# Digital_IO.net
KiCad netlist of a schematic drawn in Altium Designer
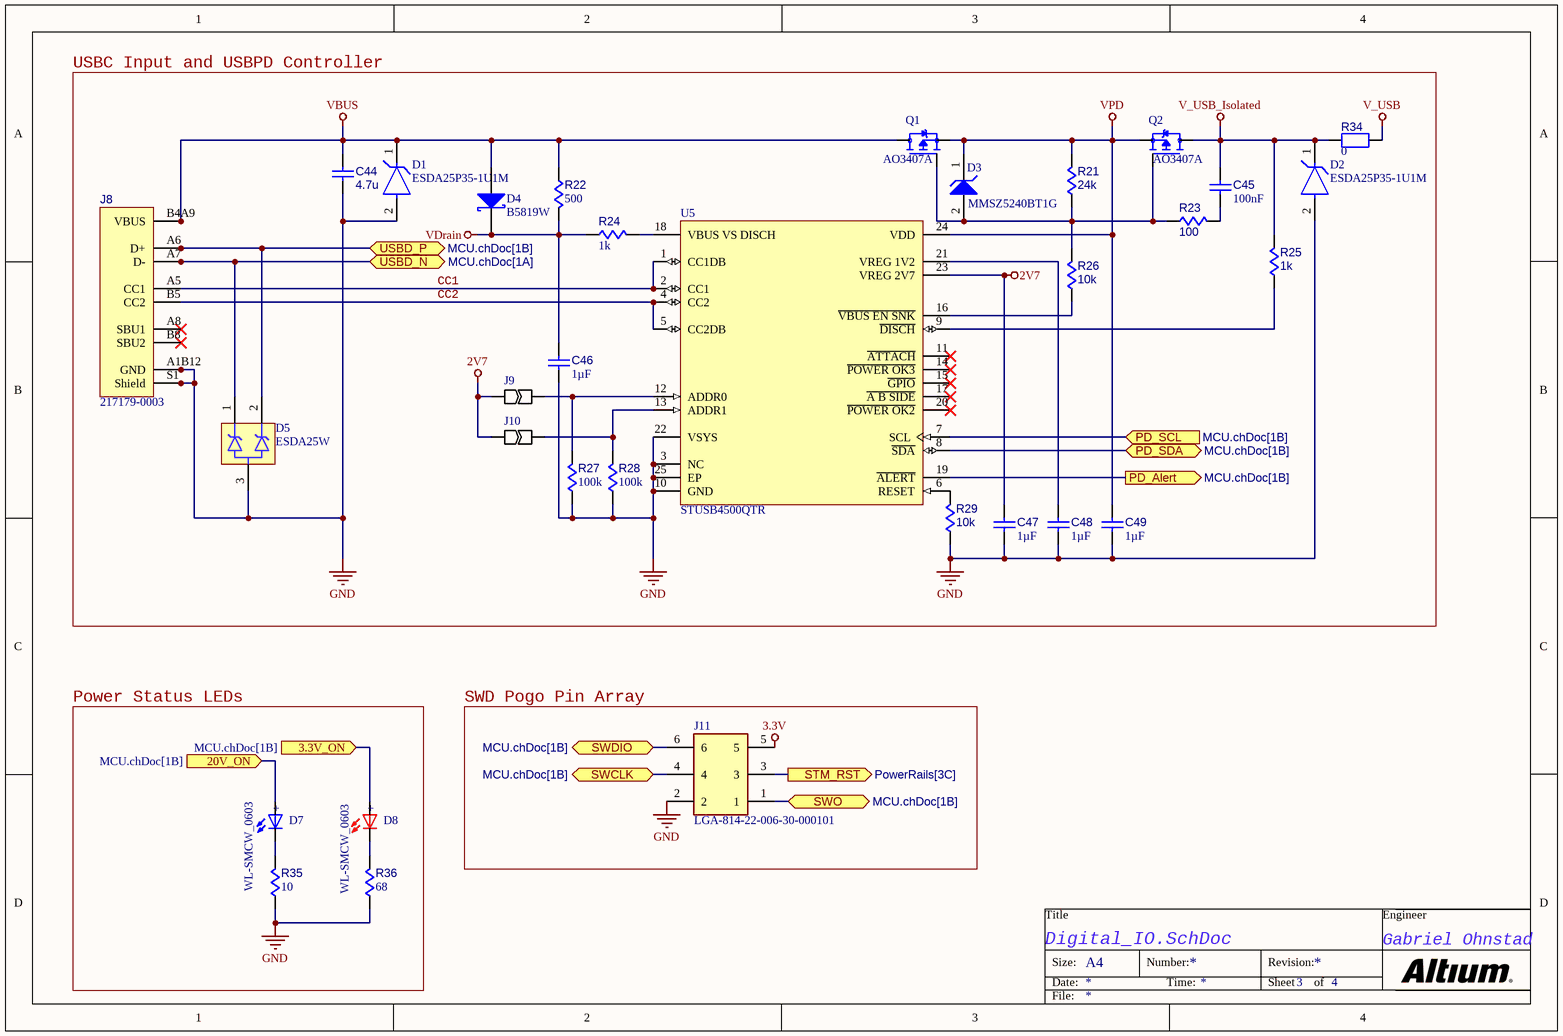
[diagram p0: Digital_IO.SchDoc]

(export (version "E")
  (design (tool "Eeschema 10.0.6"))
  (components
    (comp (ref "C44")
      (value "4.7u")
      (footprint "CAPC0805(2012)145_L")
      (description "Capacitor")
      (fields (field (name "Comment") "Capacitors,0805,4.7u,50V"))
      (libsource (lib "Gabriel A Ohnstad") (part "CAP-NP-2"))
    )
    (comp (ref "C45")
      (value "100nF")
      (footprint "CAPC0402(1005)60_L")
      (description "Chip Capacitor, 100nF +/-20%, 25V, 0402, Thickness 0.6 mm")
      (fields (field (name "TOLERANCE") "10%") (field (name "Comment") "Capacitor 100nF +/-20% 25V 0402"))
      (libsource (lib "Gabriel A Ohnstad") (part "CAP-NP-2"))
    )
    (comp (ref "C46")
      (value "1µF")
      (footprint "CAPC2013X145X50ML20T25")
      (description "Chip Capacitor, 1 uF, +/-10%, 25 V, 0805 (2012 Metric)")
      (fields (field (name "TOLERANCE") "10%") (field (name "Comment") "Capacitor 1 uF +/- 10% 25 V 0805"))
      (libsource (lib "Gabriel A Ohnstad") (part "CAP-NP-2"))
    )
    (comp (ref "C47")
      (value "1µF")
      (footprint "CAPC0402(1005)60_L")
      (description "Chip Capacitor, 1µF +/-20%, 10V, 0402, Thickness 0.6 mm")
      (fields (field (name "TOLERANCE") "10%") (field (name "Comment") "Capacitor 1µF +/-20% 10V 0402"))
      (libsource (lib "Gabriel A Ohnstad") (part "CAP-NP-2"))
    )
    (comp (ref "C48")
      (value "1µF")
      (footprint "CAPC0402(1005)60_L")
      (description "Chip Capacitor, 1µF +/-20%, 10V, 0402, Thickness 0.6 mm")
      (fields (field (name "TOLERANCE") "10%") (field (name "Comment") "Capacitor 1µF +/-20% 10V 0402"))
      (libsource (lib "Gabriel A Ohnstad") (part "CAP-NP-2"))
    )
    (comp (ref "C49")
      (value "1µF")
      (footprint "CAPC2013X145X50ML20T25")
      (description "Chip Capacitor, 1 uF, +/-10%, 25 V, 0805 (2012 Metric)")
      (fields (field (name "TOLERANCE") "10%") (field (name "Comment") "Capacitor 1 uF +/- 10% 25 V 0805"))
      (libsource (lib "Gabriel A Ohnstad") (part "CAP-NP-2"))
    )
    (comp (ref "D1")
      (value "ESDA25P35-1U1M")
      (footprint "FP-QFN_1610-MFG")
      (description "TVS DIODE 22V 41V 1610")
      (fields
        (field (name "OCTOPART") "https://octopart.com/esda25p35-1u1m-stmicroelectronics-75302699")
        (field (name "MANUFACTURER") "STMicroelectronics")
      )
      (libsource (lib "Altium Content Vault") (part "f813f71cba58e380607f5dd3caf9714"))
    )
    (comp (ref "D2")
      (value "ESDA25P35-1U1M")
      (footprint "FP-QFN_1610-MFG")
      (description "TVS DIODE 22V 41V 1610")
      (fields
        (field (name "OCTOPART") "https://octopart.com/esda25p35-1u1m-stmicroelectronics-75302699")
        (field (name "MANUFACTURER") "STMicroelectronics")
      )
      (libsource (lib "Altium Content Vault") (part "f813f71cba58e380607f5dd3caf9714"))
    )
    (comp (ref "D3")
      (value "MMSZ5240BT1G")
      (footprint "ONSC-SOD-123-2-425-04_V")
      (description "Zener Voltage Regulator, 500 mW, 2-Pin SOD-123, Pb-Free, Tape and Reel")
      (fields (field (name "MANUFACTURER") "On Semiconductor"))
      (libsource (lib "Altium Content Vault") (part "ONSC-K1A2-2"))
    )
    (comp (ref "D4")
      (value "B5819W")
      (footprint "MCC-SOD123_V")
      (description "Schottky Barrier Rectifier, 40 V, 1 A, -65 to 125 degC, 2-Pin SOD123, RoHS, Tape and Reel")
      (fields (field (name "MANUFACTURER") "Micro Commercial Components"))
      (libsource (lib "Gabriel A Ohnstad") (part "DSKY-AK-2"))
    )
    (comp (ref "D5")
      (value "ESDA25W")
      (footprint "FP-SOT323-3L-IPC_C")
      (description "25V 400W 25V 24V SOT-323-3L ESD and Surge Protection (TVS/ESD) ROHS")
      (libsource (lib "Gabriel A Ohnstad") (part "dab4d306e483478a9de7b7922f83869"))
    )
    (comp (ref "D7")
      (value "WL-SMCW_0603")
      (footprint "WL-SMCW_0603")
      (description "0603, Blue Typ.(@20mA): 470nm, 145mcd, 3.2V, 140Â° InGaN")
      (fields (field (name "MP") "150060BS75000") (field (name "MF") "Wurth Electronics"))
      (libsource (lib "Gabriel A Ohnstad") (part "WL-SMCW_0603"))
    )
    (comp (ref "D8")
      (value "WL-SMCW_0603")
      (footprint "WL-SMCW_0603")
      (description "0603, Red Typ.(@20mA): 625nm, 250mcd, 2.0V, 140Â° AlInGaP")
      (fields (field (name "MP") "150060RS75000") (field (name "MF") "Wurth Electronics"))
      (libsource (lib "") (part "WL-SMCW_0603_1"))
    )
    (comp (ref "J8")
      (value "217179-0003")
      (footprint "217179-0003-Footprint-1")
      (description "Conn USB Type C RCP 16 POS 0.5mm Solder RA SMD 16 Terminal 1 Port USB T/R")
      (fields (field (name "MANUFACTURER") "Molex"))
      (libsource (lib "Gabriel A Ohnstad") (part "217179-0003-Symbol-1"))
    )
    (comp (ref "J9")
      (value "JUMPER")
      (footprint "JUMPER")
      (libsource (lib "Gabriel A Ohnstad") (part "JUMPER"))
    )
    (comp (ref "J10")
      (value "JUMPER")
      (footprint "JUMPER")
      (libsource (lib "Gabriel A Ohnstad") (part "JUMPER"))
    )
    (comp (ref "J11")
      (value "LGA-814-22-006-30-000101")
      (footprint "Alignment-8142200630000101")
      (description "MILL MAX - 814-22-006-30-000101 - CONNECTOR, HEADER, 2.54MM, 6POS, SMT")
      (fields
        (field (name "MOUSER PART NUMBER") "575-8142200630000101")
        (field (name "MANUFACTURER_PART_NUMBER") "814-22-006-30-000101")
      )
      (libsource (lib "Gabriel A Ohnstad") (part "Copy of 814-22-006-30-000101"))
    )
    (comp (ref "Q1")
      (value "AO3407A")
      (footprint "SOT95P280X125-3N")
      (description "P-Channel 30 V 4.3A (Ta) 1.4W (Ta) Surface Mount SOT-23-3")
      (fields (field (name "MF") "Alpha &"))
      (libsource (lib "Gabriel A Ohnstad") (part "AO3407A"))
    )
    (comp (ref "Q2")
      (value "AO3407A")
      (footprint "SOT95P280X125-3N")
      (description "P-Channel 30 V 4.3A (Ta) 1.4W (Ta) Surface Mount SOT-23-3")
      (fields (field (name "MF") "Alpha &"))
      (libsource (lib "Gabriel A Ohnstad") (part "AO3407A"))
    )
    (comp (ref "R21")
      (value "24k")
      (footprint "RESC0402(1005)_L")
      (description "Resistor")
      (fields (field (name "Comment") "Resistors,0402,24k"))
      (libsource (lib "Gabriel A Ohnstad") (part "RES-2"))
    )
    (comp (ref "R22")
      (value "500")
      (footprint "RESC0603(1608)_L")
      (description "Resistor")
      (fields (field (name "Comment") "Resistors,0603,500"))
      (libsource (lib "Gabriel A Ohnstad") (part "RES-2"))
    )
    (comp (ref "R23")
      (value "100")
      (footprint "RESC0402(1005)_L")
      (description "Resistor")
      (fields (field (name "Comment") "Resistors,0402,100"))
      (libsource (lib "Gabriel A Ohnstad") (part "RES-2"))
    )
    (comp (ref "R24")
      (value "1k")
      (footprint "RESC0603(1608)_L")
      (description "Resistor")
      (fields (field (name "Comment") "Resistors,0603,1k"))
      (libsource (lib "Gabriel A Ohnstad") (part "RES-2"))
    )
    (comp (ref "R25")
      (value "1k")
      (footprint "RESC0402(1005)_L")
      (description "Resistor")
      (fields (field (name "Comment") "Resistors,0402,1k"))
      (libsource (lib "Gabriel A Ohnstad") (part "RES-2"))
    )
    (comp (ref "R26")
      (value "10k")
      (footprint "RESC0402(1005)_L")
      (description "Resistor")
      (fields (field (name "Comment") "Resistors,0402,10k"))
      (libsource (lib "Gabriel A Ohnstad") (part "RES-2"))
    )
    (comp (ref "R27")
      (value "100k")
      (footprint "RESC0402(1005)_L")
      (description "Resistor, Bootstrap")
      (fields (field (name "Comment") "Resistors,0402,100k"))
      (libsource (lib "Gabriel A Ohnstad") (part "RES-2"))
    )
    (comp (ref "R28")
      (value "100k")
      (footprint "RESC0402(1005)_L")
      (description "Resistor, Bootstrap")
      (fields (field (name "Comment") "Resistors,0402,100k"))
      (libsource (lib "Gabriel A Ohnstad") (part "RES-2"))
    )
    (comp (ref "R29")
      (value "10k")
      (footprint "RESC0402(1005)_L")
      (description "Resistor, Bootstrap")
      (fields (field (name "Comment") "Resistors,0402,10k"))
      (libsource (lib "Gabriel A Ohnstad") (part "RES-2"))
    )
    (comp (ref "R34")
      (value "0")
      (footprint "RESC0805(2012)_L")
      (description "HCJ Series 0805 Jumper Surface Mount Chip Resistor")
      (fields (field (name "Comment") "HCJ0805ZT0R00"))
      (libsource (lib "") (part "RES-2_1"))
    )
    (comp (ref "R35")
      (value "10")
      (footprint "RESC0402(1005)_L")
      (description "Resistor, Bootstrap")
      (fields (field (name "Comment") "Resistors,0402,10"))
      (libsource (lib "Gabriel A Ohnstad") (part "RES-2"))
    )
    (comp (ref "R36")
      (value "68")
      (footprint "RESC0402(1005)_L")
      (description "Resistor, Bootstrap")
      (fields (field (name "Comment") "Resistors,0402,68"))
      (libsource (lib "Gabriel A Ohnstad") (part "RES-2"))
    )
    (comp (ref "U5")
      (value "STUSB4500QTR")
      (footprint "FP-QFN-24-EP_4x4-MFG")
      (description "Super Speed USB Controller USB 1.2/USB 2.0 5V/9V/12V/15V/18V T/R 24-Pin QFN EP")
      (libsource (lib "Gabriel A Ohnstad") (part "STUSB4500QTR"))
    )
  )
  (nets
    (net (code "1") (name "/3.3V_ON") (class "Default")
      (node (ref "D8") (pin "2") (pinfunction "POS_2") (pintype "passive"))
    )
    (net (code "2") (name "/20V_ON") (class "Default")
      (node (ref "D7") (pin "2") (pinfunction "POS_2") (pintype "passive"))
    )
    (net (code "3") (name "/CC1") (class "Default")
      (node (ref "J8") (pin "A5") (pinfunction "CC1_A5") (pintype "passive"))
      (node (ref "U5") (pin "1") (pinfunction "CC1DB_1") (pintype "bidirectional"))
      (node (ref "U5") (pin "2") (pinfunction "CC1_2") (pintype "bidirectional"))
    )
    (net (code "4") (name "/CC2") (class "Default")
      (node (ref "J8") (pin "B5") (pinfunction "CC2_B5") (pintype "passive"))
      (node (ref "U5") (pin "4") (pinfunction "CC2_4") (pintype "bidirectional"))
      (node (ref "U5") (pin "5") (pinfunction "CC2DB_5") (pintype "bidirectional"))
    )
    (net (code "5") (name "/PD_Alert") (class "Default")
      (node (ref "U5") (pin "19") (pinfunction "~{ALERT}_19") (pintype "open_collector"))
    )
    (net (code "6") (name "/PD_SCL") (class "Default")
      (node (ref "U5") (pin "7") (pinfunction "SCL_7") (pintype "input"))
    )
    (net (code "7") (name "/PD_SDA") (class "Default")
      (node (ref "U5") (pin "8") (pinfunction "~{SDA}_8") (pintype "bidirectional"))
    )
    (net (code "8") (name "/STM_RST") (class "Default")
      (node (ref "J11") (pin "3") (pinfunction "3_3") (pintype "passive"))
    )
    (net (code "9") (name "/SWCLK") (class "Default")
      (node (ref "J11") (pin "4") (pinfunction "4_4") (pintype "passive"))
    )
    (net (code "10") (name "/SWDIO") (class "Default")
      (node (ref "J11") (pin "6") (pinfunction "6_6") (pintype "passive"))
    )
    (net (code "11") (name "/SWO") (class "Default")
      (node (ref "J11") (pin "1") (pinfunction "1_1") (pintype "passive"))
    )
    (net (code "12") (name "/USBD_N") (class "Default")
      (node (ref "D5") (pin "1") (pinfunction "1_CATHODE_1") (pintype "passive"))
      (node (ref "J8") (pin "A7") (pinfunction "D-_A7") (pintype "passive"))
      (node (ref "J8") (pin "B7") (pinfunction "D-_B7") (pintype "passive"))
    )
    (net (code "13") (name "/USBD_P") (class "Default")
      (node (ref "D5") (pin "2") (pinfunction "2_CATHODE_2") (pintype "passive"))
      (node (ref "J8") (pin "A6") (pinfunction "D+_A6") (pintype "passive"))
      (node (ref "J8") (pin "B6") (pinfunction "D+_B6") (pintype "passive"))
    )
    (net (code "14") (name "2V7") (class "Default")
      (node (ref "C47") (pin "2") (pinfunction "2_2") (pintype "passive"))
      (node (ref "J10") (pin "1") (pinfunction "1_1") (pintype "passive"))
      (node (ref "J9") (pin "1") (pinfunction "1_1") (pintype "passive"))
      (node (ref "U5") (pin "23") (pinfunction "VREG_2V7_23") (pintype "power_in"))
    )
    (net (code "15") (name "3.3V") (class "Default")
      (node (ref "J11") (pin "5") (pinfunction "5_5") (pintype "passive"))
    )
    (net (code "16") (name "GND") (class "Default")
      (node (ref "C44") (pin "1") (pinfunction "1_1") (pintype "passive"))
      (node (ref "C46") (pin "1") (pinfunction "1_1") (pintype "passive"))
      (node (ref "C47") (pin "1") (pinfunction "1_1") (pintype "passive"))
      (node (ref "C48") (pin "1") (pinfunction "1_1") (pintype "passive"))
      (node (ref "C49") (pin "1") (pinfunction "1_1") (pintype "passive"))
      (node (ref "D1") (pin "2") (pinfunction "A_2") (pintype "passive"))
      (node (ref "D2") (pin "2") (pinfunction "A_2") (pintype "passive"))
      (node (ref "D5") (pin "3") (pinfunction "COMMON_ANODE_3") (pintype "passive"))
      (node (ref "J11") (pin "2") (pinfunction "2_2") (pintype "passive"))
      (node (ref "J8") (pin "A1B12") (pinfunction "GND_A1B12") (pintype "passive"))
      (node (ref "J8") (pin "B1A12") (pinfunction "GND_B1A12") (pintype "passive"))
      (node (ref "J8") (pin "S1") (pinfunction "Shield_S1") (pintype "passive"))
      (node (ref "J8") (pin "S2") (pinfunction "Shield_S2") (pintype "passive"))
      (node (ref "J8") (pin "S3") (pinfunction "Shield_S3") (pintype "passive"))
      (node (ref "J8") (pin "S4") (pinfunction "Shield_S4") (pintype "passive"))
      (node (ref "R27") (pin "1") (pinfunction "1_1") (pintype "passive"))
      (node (ref "R28") (pin "1") (pinfunction "1_1") (pintype "passive"))
      (node (ref "R29") (pin "1") (pinfunction "1_1") (pintype "passive"))
      (node (ref "R35") (pin "1") (pinfunction "1_1") (pintype "passive"))
      (node (ref "R36") (pin "1") (pinfunction "1_1") (pintype "passive"))
      (node (ref "U5") (pin "10") (pinfunction "GND_10") (pintype "power_in"))
      (node (ref "U5") (pin "22") (pinfunction "VSYS_22") (pintype "power_in"))
      (node (ref "U5") (pin "25") (pinfunction "EP_25") (pintype "power_in"))
      (node (ref "U5") (pin "3") (pinfunction "NC_3") (pintype "passive"))
    )
    (net (code "17") (name "Net-(C45-Pad2)") (class "Default")
      (node (ref "C45") (pin "2") (pinfunction "2_2") (pintype "passive"))
      (node (ref "R23") (pin "2") (pinfunction "2_2") (pintype "passive"))
    )
    (net (code "18") (name "Net-(D3-A)") (class "Default")
      (node (ref "D3") (pin "2") (pinfunction "A_2") (pintype "passive"))
      (node (ref "Q1") (pin "1") (pinfunction "G_1") (pintype "passive"))
      (node (ref "Q2") (pin "1") (pinfunction "G_1") (pintype "passive"))
      (node (ref "R21") (pin "1") (pinfunction "1_1") (pintype "passive"))
      (node (ref "R23") (pin "1") (pinfunction "1_1") (pintype "passive"))
      (node (ref "R26") (pin "2") (pinfunction "2_2") (pintype "passive"))
    )
    (net (code "19") (name "Net-(D7-NEG)") (class "Default")
      (node (ref "D7") (pin "1") (pinfunction "NEG_1") (pintype "passive"))
      (node (ref "R35") (pin "2") (pinfunction "2_2") (pintype "passive"))
    )
    (net (code "20") (name "Net-(D8-NEG)") (class "Default")
      (node (ref "D8") (pin "1") (pinfunction "NEG_1") (pintype "passive"))
      (node (ref "R36") (pin "2") (pinfunction "2_2") (pintype "passive"))
    )
    (net (code "21") (name "Net-(U5-ADDR0)") (class "Default")
      (node (ref "J9") (pin "2") (pinfunction "2_2") (pintype "passive"))
      (node (ref "R27") (pin "2") (pinfunction "2_2") (pintype "passive"))
      (node (ref "U5") (pin "12") (pinfunction "ADDR0_12") (pintype "input"))
    )
    (net (code "22") (name "Net-(U5-ADDR1)") (class "Default")
      (node (ref "J10") (pin "2") (pinfunction "2_2") (pintype "passive"))
      (node (ref "R28") (pin "2") (pinfunction "2_2") (pintype "passive"))
      (node (ref "U5") (pin "13") (pinfunction "ADDR1_13") (pintype "input"))
    )
    (net (code "23") (name "Net-(U5-RESET)") (class "Default")
      (node (ref "R29") (pin "2") (pinfunction "2_2") (pintype "passive"))
      (node (ref "U5") (pin "6") (pinfunction "RESET_6") (pintype "input"))
    )
    (net (code "24") (name "Net-(U5-VBUS_VS_DISCH)") (class "Default")
      (node (ref "R24") (pin "1") (pinfunction "1_1") (pintype "passive"))
      (node (ref "U5") (pin "18") (pinfunction "VBUS_VS_DISCH_18") (pintype "power_in"))
    )
    (net (code "25") (name "Net-(U5-VREG_1V2)") (class "Default")
      (node (ref "C48") (pin "2") (pinfunction "2_2") (pintype "passive"))
      (node (ref "U5") (pin "21") (pinfunction "VREG_1V2_21") (pintype "power_in"))
    )
    (net (code "26") (name "Net-(U5-~{DISCH})") (class "Default")
      (node (ref "R25") (pin "1") (pinfunction "1_1") (pintype "passive"))
      (node (ref "U5") (pin "9") (pinfunction "~{DISCH}_9") (pintype "bidirectional"))
    )
    (net (code "27") (name "Net-(U5-~{VBUS_EN_SNK})") (class "Default")
      (node (ref "R26") (pin "1") (pinfunction "1_1") (pintype "passive"))
      (node (ref "U5") (pin "16") (pinfunction "~{VBUS_EN_SNK}_16") (pintype "open_collector"))
    )
    (net (code "28") (name "VBUS") (class "Default")
      (node (ref "C44") (pin "2") (pinfunction "2_2") (pintype "passive"))
      (node (ref "D1") (pin "1") (pinfunction "C_1") (pintype "passive"))
      (node (ref "D4") (pin "1") (pinfunction "A_1") (pintype "passive"))
      (node (ref "J8") (pin "A4B9") (pinfunction "VBUS_A4B9") (pintype "passive"))
      (node (ref "J8") (pin "B4A9") (pinfunction "VBUS_B4A9") (pintype "passive"))
      (node (ref "Q1") (pin "3") (pinfunction "D_3") (pintype "passive"))
      (node (ref "R22") (pin "2") (pinfunction "2_2") (pintype "passive"))
    )
    (net (code "29") (name "VDrain") (class "Default")
      (node (ref "C46") (pin "2") (pinfunction "2_2") (pintype "passive"))
      (node (ref "D4") (pin "2") (pinfunction "K_2") (pintype "passive"))
      (node (ref "R22") (pin "1") (pinfunction "1_1") (pintype "passive"))
      (node (ref "R24") (pin "2") (pinfunction "2_2") (pintype "passive"))
    )
    (net (code "30") (name "VPD") (class "Default")
      (node (ref "C49") (pin "2") (pinfunction "2_2") (pintype "passive"))
      (node (ref "D3") (pin "1") (pinfunction "K_1") (pintype "passive"))
      (node (ref "Q1") (pin "2") (pinfunction "S_2") (pintype "passive"))
      (node (ref "Q2") (pin "2") (pinfunction "S_2") (pintype "passive"))
      (node (ref "R21") (pin "2") (pinfunction "2_2") (pintype "passive"))
      (node (ref "U5") (pin "24") (pinfunction "VDD_24") (pintype "power_in"))
    )
    (net (code "31") (name "V_USB") (class "Default")
      (node (ref "R34") (pin "1") (pinfunction "1_1") (pintype "passive"))
    )
    (net (code "32") (name "V_USB_Isolated") (class "Default")
      (node (ref "C45") (pin "1") (pinfunction "1_1") (pintype "passive"))
      (node (ref "D2") (pin "1") (pinfunction "C_1") (pintype "passive"))
      (node (ref "Q2") (pin "3") (pinfunction "D_3") (pintype "passive"))
      (node (ref "R25") (pin "2") (pinfunction "2_2") (pintype "passive"))
      (node (ref "R34") (pin "2") (pinfunction "2_2") (pintype "passive"))
    )
    (net (code "33") (name "unconnected-(J8-SBU1-PadA8)") (class "Default")
      (node (ref "J8") (pin "A8") (pinfunction "SBU1_A8") (pintype "passive+no_connect"))
    )
    (net (code "34") (name "unconnected-(J8-SBU2-PadB8)") (class "Default")
      (node (ref "J8") (pin "B8") (pinfunction "SBU2_B8") (pintype "passive+no_connect"))
    )
    (net (code "35") (name "unconnected-(U5-~{ATTACH}-Pad11)") (class "Default")
      (node (ref "U5") (pin "11") (pinfunction "~{ATTACH}_11") (pintype "open_collector+no_connect"))
    )
    (net (code "36") (name "unconnected-(U5-~{A_B_SIDE}-Pad17)") (class "Default")
      (node (ref "U5") (pin "17") (pinfunction "~{A_B_SIDE}_17") (pintype "open_collector+no_connect"))
    )
    (net (code "37") (name "unconnected-(U5-~{GPIO}-Pad15)") (class "Default")
      (node (ref "U5") (pin "15") (pinfunction "~{GPIO}_15") (pintype "open_collector+no_connect"))
    )
    (net (code "38") (name "unconnected-(U5-~{POWER_OK2}-Pad20)") (class "Default")
      (node (ref "U5") (pin "20") (pinfunction "~{POWER_OK2}_20") (pintype "power_in+no_connect"))
    )
    (net (code "39") (name "unconnected-(U5-~{POWER_OK3}-Pad14)") (class "Default")
      (node (ref "U5") (pin "14") (pinfunction "~{POWER_OK3}_14") (pintype "open_collector+no_connect"))
    )
  )
)
